# Indicator.net
KiCad netlist of a schematic drawn in Altium Designer
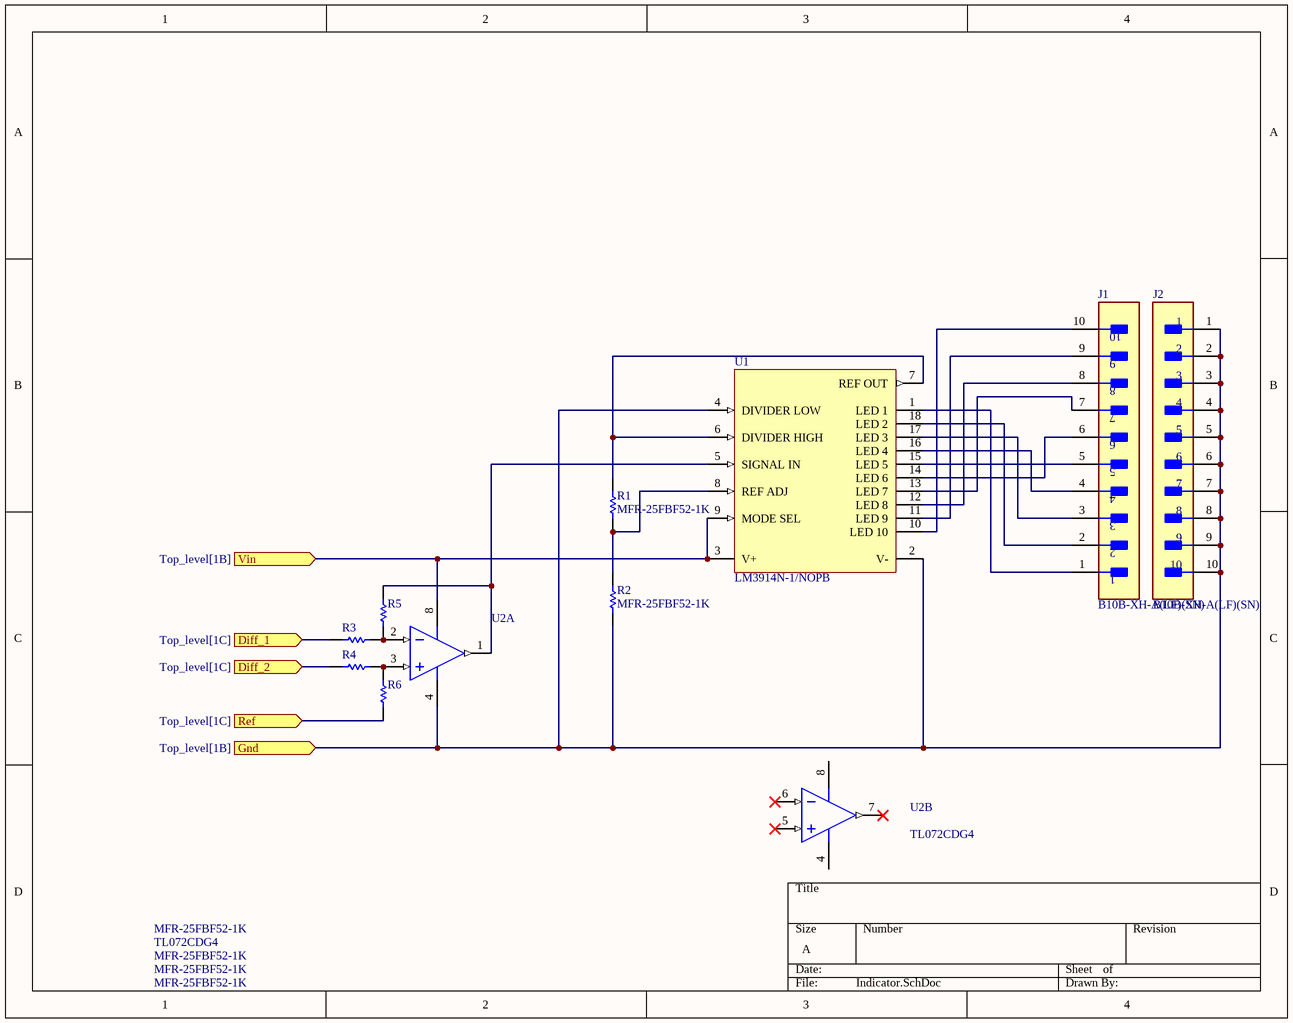
[diagram p0: Indicator.SchDoc]

(export (version "E")
  (design (tool "Eeschema 10.0.6"))
  (components
    (comp (ref "J1")
      (value "B10B-XH-A(LF)(SN)")
      (footprint "FP-B10B-XH-A_LF_SN-MFG")
      (description "CONN HEADER VERT 10POS 2.5MM")
      (libsource (lib "Altium Content Vault") (part "aee40dc8b284c03a16094555aa210be"))
    )
    (comp (ref "J2")
      (value "B10B-XH-A(LF)(SN)")
      (footprint "FP-B10B-XH-A_LF_SN-MFG")
      (description "CONN HEADER VERT 10POS 2.5MM")
      (libsource (lib "") (part "aee40dc8b284c03a16094555aa210be_1"))
    )
    (comp (ref "R1")
      (value "MFR-25FBF52-1K")
      (footprint "RESA60-630X240")
      (description "Axial Resistor, 1 KOhm, +/- 1%, 250 mW, -55 to 155 degC, 2-Pin THD, RoHS, Bulk")
      (fields (field (name "TOLERANCE") "1%"))
      (libsource (lib "Altium Content Vault") (part "RES-2"))
    )
    (comp (ref "R2")
      (value "MFR-25FBF52-1K")
      (footprint "RESA60-630X240")
      (description "Axial Resistor, 1 KOhm, +/- 1%, 250 mW, -55 to 155 degC, 2-Pin THD, RoHS, Bulk")
      (fields (field (name "TOLERANCE") "1%"))
      (libsource (lib "Altium Content Vault") (part "RES-2"))
    )
    (comp (ref "R3")
      (value "MFR-25FBF52-1K")
      (footprint "RESA60-630X240")
      (description "Axial Resistor, 1 KOhm, +/- 1%, 250 mW, -55 to 155 degC, 2-Pin THD, RoHS, Bulk")
      (fields (field (name "TOLERANCE") "1%"))
      (libsource (lib "Altium Content Vault") (part "RES-2"))
    )
    (comp (ref "R4")
      (value "MFR-25FBF52-1K")
      (footprint "RESA60-630X240")
      (description "Axial Resistor, 1 KOhm, +/- 1%, 250 mW, -55 to 155 degC, 2-Pin THD, RoHS, Bulk")
      (fields (field (name "TOLERANCE") "1%"))
      (libsource (lib "Altium Content Vault") (part "RES-2"))
    )
    (comp (ref "R5")
      (value "MFR-25FBF52-1K")
      (footprint "RESA60-630X240")
      (description "Axial Resistor, 1 KOhm, +/- 1%, 250 mW, -55 to 155 degC, 2-Pin THD, RoHS, Bulk")
      (fields (field (name "TOLERANCE") "1%"))
      (libsource (lib "Altium Content Vault") (part "RES-2"))
    )
    (comp (ref "R6")
      (value "MFR-25FBF52-1K")
      (footprint "RESA60-630X240")
      (description "Axial Resistor, 1 KOhm, +/- 1%, 250 mW, -55 to 155 degC, 2-Pin THD, RoHS, Bulk")
      (fields (field (name "TOLERANCE") "1%"))
      (libsource (lib "Altium Content Vault") (part "RES-2"))
    )
    (comp (ref "U1")
      (value "LM3914N-1/NOPB")
      (footprint "NFK0018A")
      (description "Dot/Bar Display Driver, 18-pin MDIP, Pb-Free")
      (fields (field (name "MANUFACTURER") "Texas Instruments"))
      (libsource (lib "Altium Content Vault") (part "IN-DD-LM3914-18"))
    )
    (comp (ref "U2")
      (value "TL072CDG4")
      (footprint "TI-D8_M")
      (fields (field (name "MANUFACTURER") "Texas Instruments"))
      (libsource (lib "Altium Content Vault") (part "TI-AMP-D6-2-8_D"))
    )
  )
  (nets
    (net (code "1") (name "/Diff_1") (class "Default")
      (node (ref "R3") (pin "2") (pinfunction "2_2") (pintype "passive"))
    )
    (net (code "2") (name "/Diff_2") (class "Default")
      (node (ref "R4") (pin "2") (pinfunction "2_2") (pintype "passive"))
    )
    (net (code "3") (name "/Gnd") (class "Default")
      (node (ref "J2") (pin "1") (pinfunction "1_1") (pintype "passive"))
      (node (ref "J2") (pin "10") (pinfunction "10_10") (pintype "passive"))
      (node (ref "J2") (pin "2") (pinfunction "2_2") (pintype "passive"))
      (node (ref "J2") (pin "3") (pinfunction "3_3") (pintype "passive"))
      (node (ref "J2") (pin "4") (pinfunction "4_4") (pintype "passive"))
      (node (ref "J2") (pin "5") (pinfunction "5_5") (pintype "passive"))
      (node (ref "J2") (pin "6") (pinfunction "6_6") (pintype "passive"))
      (node (ref "J2") (pin "7") (pinfunction "7_7") (pintype "passive"))
      (node (ref "J2") (pin "8") (pinfunction "8_8") (pintype "passive"))
      (node (ref "J2") (pin "9") (pinfunction "9_9") (pintype "passive"))
      (node (ref "R2") (pin "1") (pinfunction "1_1") (pintype "passive"))
      (node (ref "U1") (pin "2") (pinfunction "V-_2") (pintype "power_in"))
      (node (ref "U1") (pin "4") (pinfunction "DIVIDER_LOW_4") (pintype "input"))
      (node (ref "U2") (pin "4") (pinfunction "VCC-_4") (pintype "power_in"))
    )
    (net (code "4") (name "/Ref") (class "Default")
      (node (ref "R6") (pin "1") (pinfunction "1_1") (pintype "passive"))
    )
    (net (code "5") (name "/Vin") (class "Default")
      (node (ref "U1") (pin "3") (pinfunction "V+_3") (pintype "power_in"))
      (node (ref "U1") (pin "9") (pinfunction "MODE_SEL_9") (pintype "input"))
      (node (ref "U2") (pin "8") (pinfunction "VCC+_8") (pintype "power_in"))
    )
    (net (code "6") (name "Net-(U1-DIVIDER_HIGH)") (class "Default")
      (node (ref "R1") (pin "2") (pinfunction "2_2") (pintype "passive"))
      (node (ref "U1") (pin "6") (pinfunction "DIVIDER_HIGH_6") (pintype "input"))
      (node (ref "U1") (pin "7") (pinfunction "REF_OUT_7") (pintype "output"))
    )
    (net (code "7") (name "Net-(U1-LED_1)") (class "Default")
      (node (ref "J1") (pin "1") (pinfunction "1_1") (pintype "passive"))
      (node (ref "U1") (pin "1") (pinfunction "LED_1_1") (pintype "open_collector"))
    )
    (net (code "8") (name "Net-(U1-LED_2)") (class "Default")
      (node (ref "J1") (pin "2") (pinfunction "2_2") (pintype "passive"))
      (node (ref "U1") (pin "18") (pinfunction "LED_2_18") (pintype "open_collector"))
    )
    (net (code "9") (name "Net-(U1-LED_3)") (class "Default")
      (node (ref "J1") (pin "3") (pinfunction "3_3") (pintype "passive"))
      (node (ref "U1") (pin "17") (pinfunction "LED_3_17") (pintype "open_collector"))
    )
    (net (code "10") (name "Net-(U1-LED_4)") (class "Default")
      (node (ref "J1") (pin "4") (pinfunction "4_4") (pintype "passive"))
      (node (ref "U1") (pin "16") (pinfunction "LED_4_16") (pintype "open_collector"))
    )
    (net (code "11") (name "Net-(U1-LED_5)") (class "Default")
      (node (ref "J1") (pin "5") (pinfunction "5_5") (pintype "passive"))
      (node (ref "U1") (pin "15") (pinfunction "LED_5_15") (pintype "open_collector"))
    )
    (net (code "12") (name "Net-(U1-LED_6)") (class "Default")
      (node (ref "J1") (pin "6") (pinfunction "6_6") (pintype "passive"))
      (node (ref "U1") (pin "14") (pinfunction "LED_6_14") (pintype "open_collector"))
    )
    (net (code "13") (name "Net-(U1-LED_7)") (class "Default")
      (node (ref "J1") (pin "7") (pinfunction "7_7") (pintype "passive"))
      (node (ref "U1") (pin "13") (pinfunction "LED_7_13") (pintype "open_collector"))
    )
    (net (code "14") (name "Net-(U1-LED_8)") (class "Default")
      (node (ref "J1") (pin "8") (pinfunction "8_8") (pintype "passive"))
      (node (ref "U1") (pin "12") (pinfunction "LED_8_12") (pintype "open_collector"))
    )
    (net (code "15") (name "Net-(U1-LED_9)") (class "Default")
      (node (ref "J1") (pin "9") (pinfunction "9_9") (pintype "passive"))
      (node (ref "U1") (pin "11") (pinfunction "LED_9_11") (pintype "open_collector"))
    )
    (net (code "16") (name "Net-(U1-LED_10)") (class "Default")
      (node (ref "J1") (pin "10") (pinfunction "10_10") (pintype "passive"))
      (node (ref "U1") (pin "10") (pinfunction "LED_10_10") (pintype "open_collector"))
    )
    (net (code "17") (name "Net-(U1-REF_ADJ)") (class "Default")
      (node (ref "R1") (pin "1") (pinfunction "1_1") (pintype "passive"))
      (node (ref "R2") (pin "2") (pinfunction "2_2") (pintype "passive"))
      (node (ref "U1") (pin "8") (pinfunction "REF_ADJ_8") (pintype "input"))
    )
    (net (code "18") (name "Net-(U1-SIGNAL_IN)") (class "Default")
      (node (ref "R5") (pin "2") (pinfunction "2_2") (pintype "passive"))
      (node (ref "U1") (pin "5") (pinfunction "SIGNAL_IN_5") (pintype "input"))
      (node (ref "U2") (pin "1") (pinfunction "OUT1_1") (pintype "output"))
    )
    (net (code "19") (name "Net-(U2A-IN1+)") (class "Default")
      (node (ref "R4") (pin "1") (pinfunction "1_1") (pintype "passive"))
      (node (ref "R6") (pin "2") (pinfunction "2_2") (pintype "passive"))
      (node (ref "U2") (pin "3") (pinfunction "IN1+_3") (pintype "input"))
    )
    (net (code "20") (name "Net-(U2A-IN1-)") (class "Default")
      (node (ref "R3") (pin "1") (pinfunction "1_1") (pintype "passive"))
      (node (ref "R5") (pin "1") (pinfunction "1_1") (pintype "passive"))
      (node (ref "U2") (pin "2") (pinfunction "IN1-_2") (pintype "input"))
    )
    (net (code "21") (name "unconnected-(U2B-IN2+-Pad5)") (class "Default")
      (node (ref "U2") (pin "5") (pinfunction "IN2+_5") (pintype "input+no_connect"))
    )
    (net (code "22") (name "unconnected-(U2B-IN2--Pad6)") (class "Default")
      (node (ref "U2") (pin "6") (pinfunction "IN2-_6") (pintype "input+no_connect"))
    )
    (net (code "23") (name "unconnected-(U2B-OUT2-Pad7)") (class "Default")
      (node (ref "U2") (pin "7") (pinfunction "OUT2_7") (pintype "output+no_connect"))
    )
    (net (code "24") (name "unconnected-(U2B-VCC+-Pad8)") (class "Default")
      (node (ref "U2") (pin "8") (pinfunction "VCC+_8") (pintype "power_in"))
    )
    (net (code "25") (name "unconnected-(U2B-VCC--Pad4)") (class "Default")
      (node (ref "U2") (pin "4") (pinfunction "VCC-_4") (pintype "power_in"))
    )
  )
)
